# statuspanel.net
KiCad netlist of a schematic drawn in EAGLE
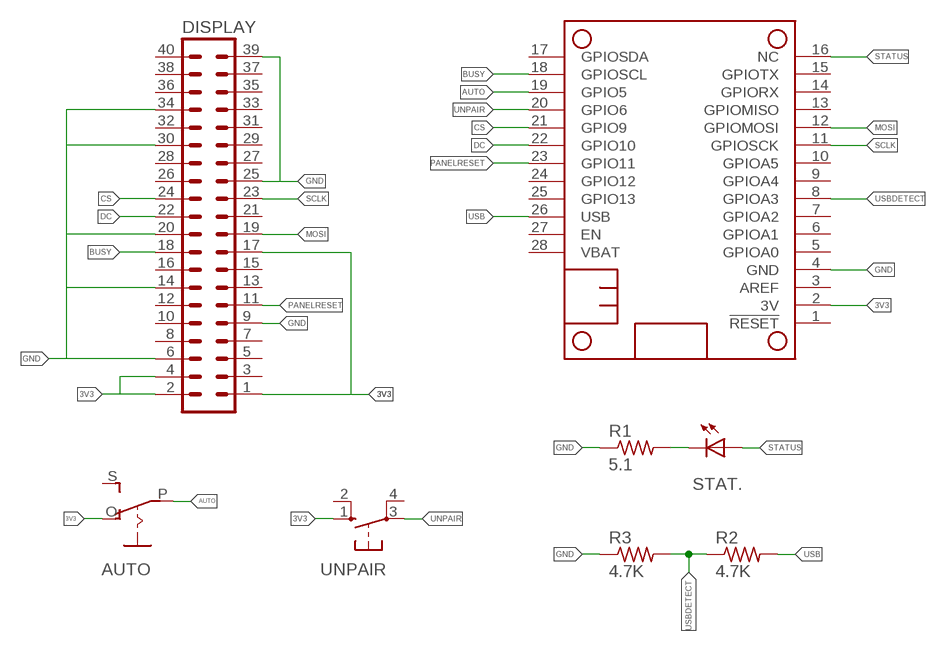
[diagram p0: schematic, sheet 1]

(export (version "E")
  (design (tool "Eeschema 10.0.6"))
  (components
    (comp (ref "AUTO")
      (value "EG1218S")
      (footprint "eagle-import:EG1218")
      (libsource (lib "eagle-import") (part "EG1218S"))
    )
    (comp (ref "DISPLAY")
      (value "MA20-2")
      (footprint "eagle-import:MA20-2")
      (libsource (lib "eagle-import") (part "MA20-2"))
    )
    (comp (ref "HUZZAH32")
      (value "FEATHERWING_NODIM")
      (footprint "eagle-import:FEATHERWING_DIM")
      (libsource (lib "eagle-import") (part "FEATHERWING_NODIM"))
    )
    (comp (ref "R1")
      (value "5.1")
      (footprint "eagle-import:0411_12")
      (libsource (lib "eagle-import") (part "R-US_0411/12"))
    )
    (comp (ref "R2")
      (value "4.7K")
      (footprint "eagle-import:0411_12")
      (libsource (lib "eagle-import") (part "R-US_0411/12"))
    )
    (comp (ref "R3")
      (value "4.7K")
      (footprint "eagle-import:0411_12")
      (libsource (lib "eagle-import") (part "R-US_0411/12"))
    )
    (comp (ref "STAT.")
      (value "LED3MM")
      (footprint "eagle-import:LED3MM")
      (libsource (lib "eagle-import") (part "LED3MM"))
    )
    (comp (ref "UNPAIR")
      (value "10-XX")
      (footprint "eagle-import:B3F-10XX")
      (fields (field (name "MPN") "B3F-1000"))
      (libsource (lib "eagle-import") (part "10-XX"))
    )
  )
  (nets
    (net (code "1") (name "/VBAT") (class "Default")
      (node (ref "HUZZAH32") (pin "28") (pinfunction "VBAT_28") (pintype "power_in"))
    )
    (net (code "2") (name "3V3") (class "Default")
      (node (ref "AUTO") (pin "O") (pinfunction "O_O") (pintype "passive"))
      (node (ref "DISPLAY") (pin "1") (pinfunction "1_1") (pintype "passive"))
      (node (ref "DISPLAY") (pin "17") (pinfunction "17_17") (pintype "passive"))
      (node (ref "DISPLAY") (pin "2") (pinfunction "2_2") (pintype "passive"))
      (node (ref "DISPLAY") (pin "4") (pinfunction "4_4") (pintype "passive"))
      (node (ref "HUZZAH32") (pin "2") (pinfunction "3V_2") (pintype "power_in"))
      (node (ref "UNPAIR") (pin "1") (pinfunction "S_1") (pintype "passive"))
    )
    (net (code "3") (name "AUTO") (class "Default")
      (node (ref "AUTO") (pin "P") (pinfunction "P_P") (pintype "passive"))
      (node (ref "HUZZAH32") (pin "19") (pinfunction "GPIO5_19") (pintype "bidirectional"))
    )
    (net (code "4") (name "BUSY") (class "Default")
      (node (ref "DISPLAY") (pin "18") (pinfunction "18_18") (pintype "passive"))
      (node (ref "HUZZAH32") (pin "18") (pinfunction "GPIOSCL_18") (pintype "bidirectional"))
    )
    (net (code "5") (name "CS") (class "Default")
      (node (ref "DISPLAY") (pin "24") (pinfunction "24_24") (pintype "passive"))
      (node (ref "HUZZAH32") (pin "21") (pinfunction "GPIO9_21") (pintype "bidirectional"))
    )
    (net (code "6") (name "DC") (class "Default")
      (node (ref "DISPLAY") (pin "22") (pinfunction "22_22") (pintype "passive"))
      (node (ref "HUZZAH32") (pin "22") (pinfunction "GPIO10_22") (pintype "bidirectional"))
    )
    (net (code "7") (name "GND") (class "Default")
      (node (ref "DISPLAY") (pin "14") (pinfunction "14_14") (pintype "passive"))
      (node (ref "DISPLAY") (pin "20") (pinfunction "20_20") (pintype "passive"))
      (node (ref "DISPLAY") (pin "25") (pinfunction "25_25") (pintype "passive"))
      (node (ref "DISPLAY") (pin "30") (pinfunction "30_30") (pintype "passive"))
      (node (ref "DISPLAY") (pin "34") (pinfunction "34_34") (pintype "passive"))
      (node (ref "DISPLAY") (pin "39") (pinfunction "39_39") (pintype "passive"))
      (node (ref "DISPLAY") (pin "6") (pinfunction "6_6") (pintype "passive"))
      (node (ref "DISPLAY") (pin "9") (pinfunction "9_9") (pintype "passive"))
      (node (ref "HUZZAH32") (pin "4") (pinfunction "GND_4") (pintype "power_in"))
      (node (ref "R1") (pin "1") (pinfunction "1_1") (pintype "passive"))
      (node (ref "R3") (pin "1") (pinfunction "1_1") (pintype "passive"))
    )
    (net (code "8") (name "MOSI") (class "Default")
      (node (ref "DISPLAY") (pin "19") (pinfunction "19_19") (pintype "passive"))
      (node (ref "HUZZAH32") (pin "12") (pinfunction "GPIOMOSI_12") (pintype "bidirectional"))
    )
    (net (code "9") (name "Net-(STAT.-C)") (class "Default")
      (node (ref "R1") (pin "2") (pinfunction "2_2") (pintype "passive"))
      (node (ref "STAT.") (pin "K") (pinfunction "C_K") (pintype "passive"))
    )
    (net (code "10") (name "PANELRESET") (class "Default")
      (node (ref "DISPLAY") (pin "11") (pinfunction "11_11") (pintype "passive"))
      (node (ref "HUZZAH32") (pin "23") (pinfunction "GPIO11_23") (pintype "bidirectional"))
    )
    (net (code "11") (name "SCLK") (class "Default")
      (node (ref "DISPLAY") (pin "23") (pinfunction "23_23") (pintype "passive"))
      (node (ref "HUZZAH32") (pin "11") (pinfunction "GPIOSCK_11") (pintype "bidirectional"))
    )
    (net (code "12") (name "STATUS") (class "Default")
      (node (ref "HUZZAH32") (pin "16") (pinfunction "NC_16") (pintype "passive"))
      (node (ref "STAT.") (pin "A") (pinfunction "A_A") (pintype "passive"))
    )
    (net (code "13") (name "UNPAIR") (class "Default")
      (node (ref "HUZZAH32") (pin "20") (pinfunction "GPIO6_20") (pintype "bidirectional"))
      (node (ref "UNPAIR") (pin "3") (pinfunction "P_3") (pintype "passive"))
    )
    (net (code "14") (name "USB") (class "Default")
      (node (ref "HUZZAH32") (pin "26") (pinfunction "USB_26") (pintype "power_in"))
      (node (ref "R2") (pin "2") (pinfunction "2_2") (pintype "passive"))
    )
    (net (code "15") (name "USBDETECT") (class "Default")
      (node (ref "HUZZAH32") (pin "8") (pinfunction "GPIOA3_8") (pintype "bidirectional"))
      (node (ref "R2") (pin "1") (pinfunction "1_1") (pintype "passive"))
      (node (ref "R3") (pin "2") (pinfunction "2_2") (pintype "passive"))
    )
    (net (code "16") (name "unconnected-(AUTO-PadS)") (class "Default")
      (node (ref "AUTO") (pin "S") (pinfunction "S_S") (pintype "passive"))
    )
    (net (code "17") (name "unconnected-(DISPLAY-Pad3)") (class "Default")
      (node (ref "DISPLAY") (pin "3") (pinfunction "3_3") (pintype "passive"))
    )
    (net (code "18") (name "unconnected-(DISPLAY-Pad5)") (class "Default")
      (node (ref "DISPLAY") (pin "5") (pinfunction "5_5") (pintype "passive"))
    )
    (net (code "19") (name "unconnected-(DISPLAY-Pad7)") (class "Default")
      (node (ref "DISPLAY") (pin "7") (pinfunction "7_7") (pintype "passive"))
    )
    (net (code "20") (name "unconnected-(DISPLAY-Pad8)") (class "Default")
      (node (ref "DISPLAY") (pin "8") (pinfunction "8_8") (pintype "passive"))
    )
    (net (code "21") (name "unconnected-(DISPLAY-Pad10)") (class "Default")
      (node (ref "DISPLAY") (pin "10") (pinfunction "10_10") (pintype "passive"))
    )
    (net (code "22") (name "unconnected-(DISPLAY-Pad12)") (class "Default")
      (node (ref "DISPLAY") (pin "12") (pinfunction "12_12") (pintype "passive"))
    )
    (net (code "23") (name "unconnected-(DISPLAY-Pad13)") (class "Default")
      (node (ref "DISPLAY") (pin "13") (pinfunction "13_13") (pintype "passive"))
    )
    (net (code "24") (name "unconnected-(DISPLAY-Pad15)") (class "Default")
      (node (ref "DISPLAY") (pin "15") (pinfunction "15_15") (pintype "passive"))
    )
    (net (code "25") (name "unconnected-(DISPLAY-Pad16)") (class "Default")
      (node (ref "DISPLAY") (pin "16") (pinfunction "16_16") (pintype "passive"))
    )
    (net (code "26") (name "unconnected-(DISPLAY-Pad21)") (class "Default")
      (node (ref "DISPLAY") (pin "21") (pinfunction "21_21") (pintype "passive"))
    )
    (net (code "27") (name "unconnected-(DISPLAY-Pad26)") (class "Default")
      (node (ref "DISPLAY") (pin "26") (pinfunction "26_26") (pintype "passive"))
    )
    (net (code "28") (name "unconnected-(DISPLAY-Pad27)") (class "Default")
      (node (ref "DISPLAY") (pin "27") (pinfunction "27_27") (pintype "passive"))
    )
    (net (code "29") (name "unconnected-(DISPLAY-Pad28)") (class "Default")
      (node (ref "DISPLAY") (pin "28") (pinfunction "28_28") (pintype "passive"))
    )
    (net (code "30") (name "unconnected-(DISPLAY-Pad29)") (class "Default")
      (node (ref "DISPLAY") (pin "29") (pinfunction "29_29") (pintype "passive"))
    )
    (net (code "31") (name "unconnected-(DISPLAY-Pad31)") (class "Default")
      (node (ref "DISPLAY") (pin "31") (pinfunction "31_31") (pintype "passive"))
    )
    (net (code "32") (name "unconnected-(DISPLAY-Pad32)") (class "Default")
      (node (ref "DISPLAY") (pin "32") (pinfunction "32_32") (pintype "passive"))
    )
    (net (code "33") (name "unconnected-(DISPLAY-Pad33)") (class "Default")
      (node (ref "DISPLAY") (pin "33") (pinfunction "33_33") (pintype "passive"))
    )
    (net (code "34") (name "unconnected-(DISPLAY-Pad35)") (class "Default")
      (node (ref "DISPLAY") (pin "35") (pinfunction "35_35") (pintype "passive"))
    )
    (net (code "35") (name "unconnected-(DISPLAY-Pad36)") (class "Default")
      (node (ref "DISPLAY") (pin "36") (pinfunction "36_36") (pintype "passive"))
    )
    (net (code "36") (name "unconnected-(DISPLAY-Pad37)") (class "Default")
      (node (ref "DISPLAY") (pin "37") (pinfunction "37_37") (pintype "passive"))
    )
    (net (code "37") (name "unconnected-(DISPLAY-Pad38)") (class "Default")
      (node (ref "DISPLAY") (pin "38") (pinfunction "38_38") (pintype "passive"))
    )
    (net (code "38") (name "unconnected-(DISPLAY-Pad40)") (class "Default")
      (node (ref "DISPLAY") (pin "40") (pinfunction "40_40") (pintype "passive"))
    )
    (net (code "39") (name "unconnected-(HUZZAH32-AREF-Pad3)") (class "Default")
      (node (ref "HUZZAH32") (pin "3") (pinfunction "AREF_3") (pintype "passive"))
    )
    (net (code "40") (name "unconnected-(HUZZAH32-EN-Pad27)") (class "Default")
      (node (ref "HUZZAH32") (pin "27") (pinfunction "EN_27") (pintype "passive"))
    )
    (net (code "41") (name "unconnected-(HUZZAH32-GPIO12-Pad24)") (class "Default")
      (node (ref "HUZZAH32") (pin "24") (pinfunction "GPIO12_24") (pintype "bidirectional"))
    )
    (net (code "42") (name "unconnected-(HUZZAH32-GPIO13-Pad25)") (class "Default")
      (node (ref "HUZZAH32") (pin "25") (pinfunction "GPIO13_25") (pintype "bidirectional"))
    )
    (net (code "43") (name "unconnected-(HUZZAH32-GPIOA0-Pad5)") (class "Default")
      (node (ref "HUZZAH32") (pin "5") (pinfunction "GPIOA0_5") (pintype "bidirectional"))
    )
    (net (code "44") (name "unconnected-(HUZZAH32-GPIOA1-Pad6)") (class "Default")
      (node (ref "HUZZAH32") (pin "6") (pinfunction "GPIOA1_6") (pintype "bidirectional"))
    )
    (net (code "45") (name "unconnected-(HUZZAH32-GPIOA2-Pad7)") (class "Default")
      (node (ref "HUZZAH32") (pin "7") (pinfunction "GPIOA2_7") (pintype "bidirectional"))
    )
    (net (code "46") (name "unconnected-(HUZZAH32-GPIOA4-Pad9)") (class "Default")
      (node (ref "HUZZAH32") (pin "9") (pinfunction "GPIOA4_9") (pintype "bidirectional"))
    )
    (net (code "47") (name "unconnected-(HUZZAH32-GPIOA5-Pad10)") (class "Default")
      (node (ref "HUZZAH32") (pin "10") (pinfunction "GPIOA5_10") (pintype "bidirectional"))
    )
    (net (code "48") (name "unconnected-(HUZZAH32-GPIOMISO-Pad13)") (class "Default")
      (node (ref "HUZZAH32") (pin "13") (pinfunction "GPIOMISO_13") (pintype "bidirectional"))
    )
    (net (code "49") (name "unconnected-(HUZZAH32-GPIORX-Pad14)") (class "Default")
      (node (ref "HUZZAH32") (pin "14") (pinfunction "GPIORX_14") (pintype "bidirectional"))
    )
    (net (code "50") (name "unconnected-(HUZZAH32-GPIOSDA-Pad17)") (class "Default")
      (node (ref "HUZZAH32") (pin "17") (pinfunction "GPIOSDA_17") (pintype "bidirectional"))
    )
    (net (code "51") (name "unconnected-(HUZZAH32-GPIOTX-Pad15)") (class "Default")
      (node (ref "HUZZAH32") (pin "15") (pinfunction "GPIOTX_15") (pintype "bidirectional"))
    )
    (net (code "52") (name "unconnected-(HUZZAH32-~{RESET}-Pad1)") (class "Default")
      (node (ref "HUZZAH32") (pin "1") (pinfunction "~{RESET}_1") (pintype "input"))
    )
    (net (code "53") (name "unconnected-(UNPAIR-P1-Pad4)") (class "Default")
      (node (ref "UNPAIR") (pin "4") (pinfunction "P1_4") (pintype "passive"))
    )
    (net (code "54") (name "unconnected-(UNPAIR-S1-Pad2)") (class "Default")
      (node (ref "UNPAIR") (pin "2") (pinfunction "S1_2") (pintype "passive"))
    )
  )
)
